# noisemaker_3-0.net
KiCad netlist of a schematic drawn in EAGLE
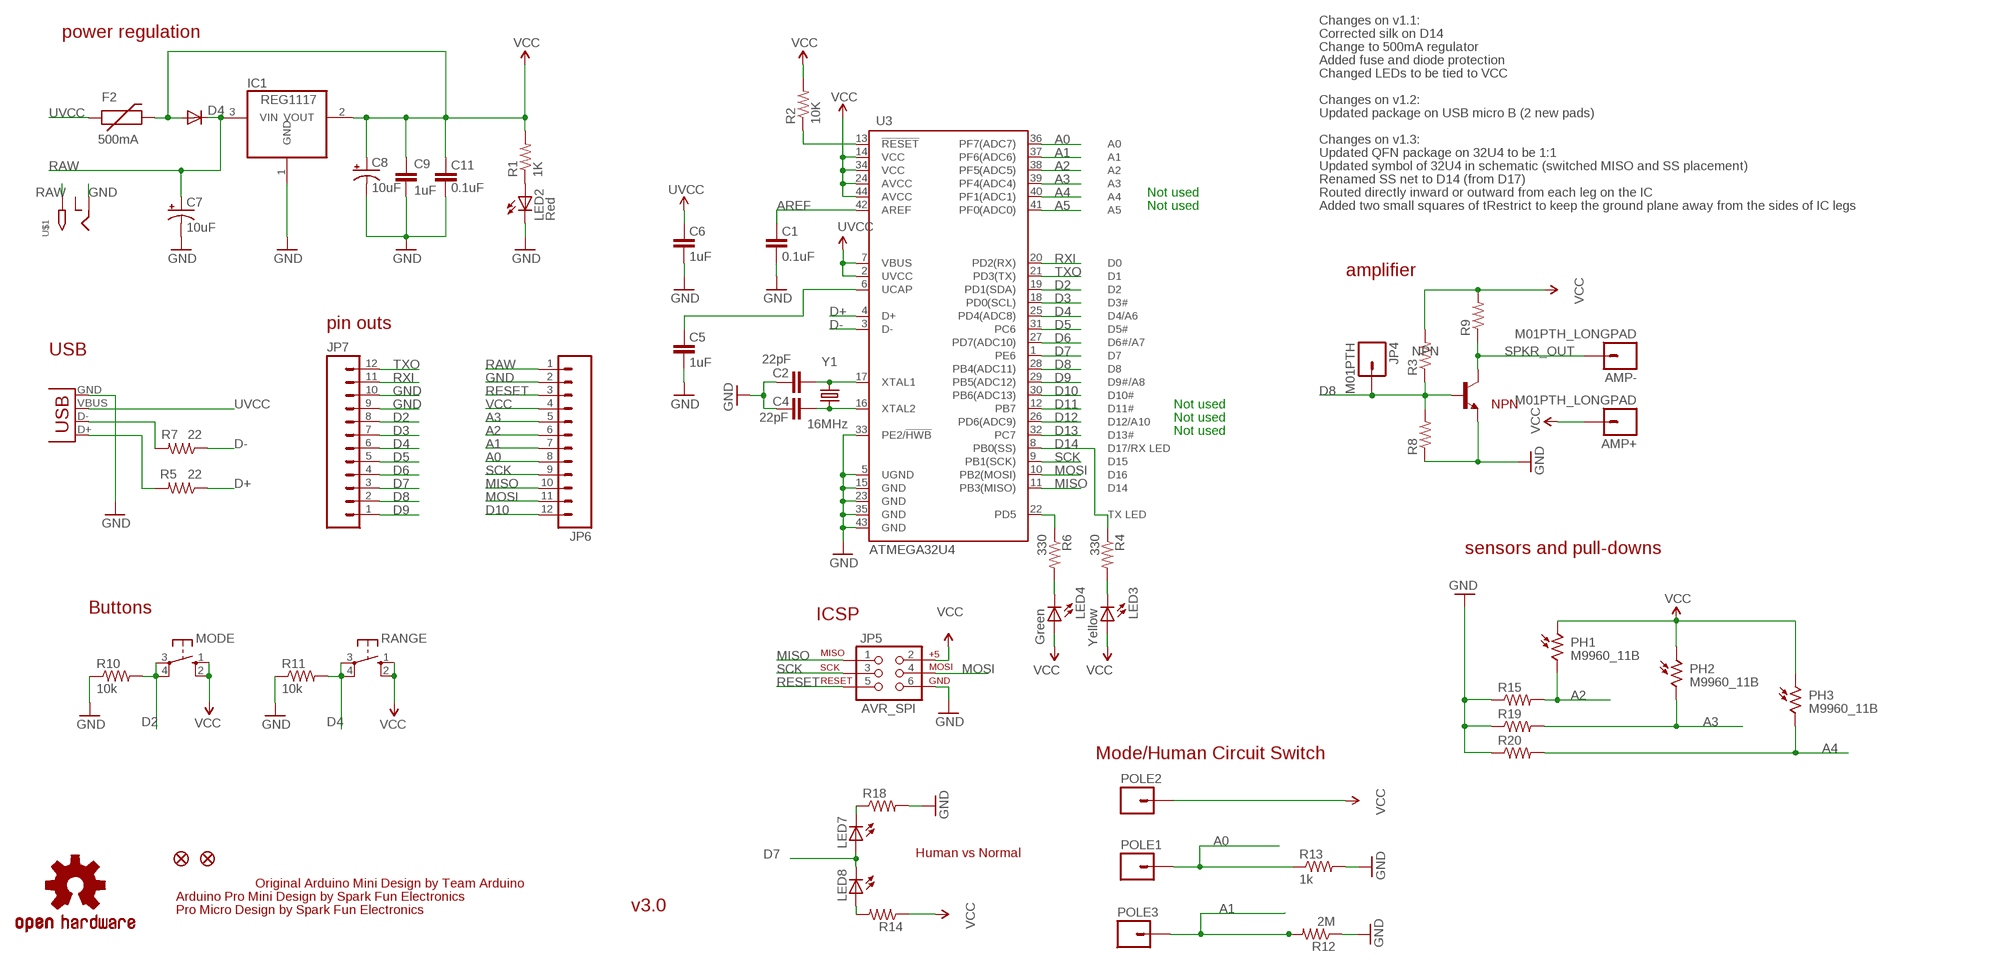
[diagram p0: schematic, sheet 1]

(export (version "E")
  (design (tool "Eeschema 10.0.6"))
  (components
    (comp (ref "AMP+")
      (value "M01PTH_LONGPAD")
      (footprint "eagle-import:1X01_LONGPAD")
      (libsource (lib "eagle-import") (part "M01PTH_LONGPAD"))
    )
    (comp (ref "AMP-")
      (value "M01PTH_LONGPAD")
      (footprint "eagle-import:1X01_LONGPAD")
      (libsource (lib "eagle-import") (part "M01PTH_LONGPAD"))
    )
    (comp (ref "C1")
      (value "0.1uF")
      (footprint "eagle-import:1206")
      (libsource (lib "eagle-import") (part "SparkFun-Capacitors_CAP1206"))
    )
    (comp (ref "C2")
      (value "22pF")
      (footprint "eagle-import:0603-CAP")
      (libsource (lib "eagle-import") (part "CAP0603-CAP"))
    )
    (comp (ref "C4")
      (value "22pF")
      (footprint "eagle-import:0603-CAP")
      (libsource (lib "eagle-import") (part "CAP0603-CAP"))
    )
    (comp (ref "C5")
      (value "1uF")
      (footprint "eagle-import:1206")
      (libsource (lib "eagle-import") (part "SparkFun-Capacitors_CAP1206"))
    )
    (comp (ref "C6")
      (value "1uF")
      (footprint "eagle-import:1206")
      (libsource (lib "eagle-import") (part "SparkFun-Capacitors_CAP1206"))
    )
    (comp (ref "C7")
      (value "10uF")
      (footprint "eagle-import:EIA3528-KIT")
      (libsource (lib "eagle-import") (part "CAP_POL3528-KIT"))
    )
    (comp (ref "C8")
      (value "10uF")
      (footprint "eagle-import:EIA3528-KIT")
      (libsource (lib "eagle-import") (part "CAP_POL3528-KIT"))
    )
    (comp (ref "C9")
      (value "1uF")
      (footprint "eagle-import:1206")
      (libsource (lib "eagle-import") (part "SparkFun-Capacitors_CAP1206"))
    )
    (comp (ref "C11")
      (value "0.1uF")
      (footprint "eagle-import:1206")
      (libsource (lib "eagle-import") (part "SparkFun-Capacitors_CAP1206"))
    )
    (comp (ref "D4")
      (value "DIODESOD")
      (footprint "eagle-import:SOD-323")
      (libsource (lib "eagle-import") (part "DIODESOD"))
    )
    (comp (ref "F2")
      (value "500mA")
      (footprint "eagle-import:PTC-1206")
      (libsource (lib "eagle-import") (part "PTCSMD"))
    )
    (comp (ref "IC1")
      (value "REG1117")
      (footprint "eagle-import:SOT223")
      (libsource (lib "eagle-import") (part "REG1117"))
    )
    (comp (ref "JP1")
      (value "FIDUCIALUFIDUCIAL")
      (footprint "eagle-import:MICRO-FIDUCIAL")
      (libsource (lib "eagle-import") (part "FIDUCIALUFIDUCIAL"))
    )
    (comp (ref "JP2")
      (value "FIDUCIALUFIDUCIAL")
      (footprint "eagle-import:MICRO-FIDUCIAL")
      (libsource (lib "eagle-import") (part "FIDUCIALUFIDUCIAL"))
    )
    (comp (ref "JP3")
      (value "USB-B")
      (footprint "eagle-import:USB-B-PTH")
      (libsource (lib "eagle-import") (part "USBPTH"))
    )
    (comp (ref "JP4")
      (value "M01PTH")
      (footprint "eagle-import:1X01")
      (libsource (lib "eagle-import") (part "M01PTH"))
    )
    (comp (ref "JP5")
      (value "AVR_SPI")
      (footprint "eagle-import:2X3")
      (libsource (lib "eagle-import") (part "AVR_SPI_PRG_6PTH"))
    )
    (comp (ref "JP6")
      (value "M12PTH")
      (footprint "eagle-import:1X12")
      (libsource (lib "eagle-import") (part "M12PTH"))
    )
    (comp (ref "JP7")
      (value "M12PTH")
      (footprint "eagle-import:1X12")
      (libsource (lib "eagle-import") (part "M12PTH"))
    )
    (comp (ref "LED2")
      (value "Red")
      (footprint "eagle-import:CHIPLED_1206")
      (libsource (lib "eagle-import") (part "LEDCHIPLED_1206"))
    )
    (comp (ref "LED3")
      (value "Yellow")
      (footprint "eagle-import:CHIPLED_1206")
      (libsource (lib "eagle-import") (part "LEDCHIPLED_1206"))
    )
    (comp (ref "LED4")
      (value "Green")
      (footprint "eagle-import:CHIPLED_1206")
      (libsource (lib "eagle-import") (part "LEDCHIPLED_1206"))
    )
    (comp (ref "LED7")
      (value "LED3MM")
      (footprint "eagle-import:LED3MM")
      (libsource (lib "eagle-import") (part "LED3MM"))
    )
    (comp (ref "LED8")
      (value "LED3MM")
      (footprint "eagle-import:LED3MM")
      (libsource (lib "eagle-import") (part "LED3MM"))
    )
    (comp (ref "MODE")
      (value "10-XX")
      (footprint "eagle-import:B3F-10XX")
      (libsource (lib "eagle-import") (part "10-XX"))
    )
    (comp (ref "NPN")
      (value "-NPN-TO220V")
      (footprint "eagle-import:TO220V")
      (libsource (lib "eagle-import") (part "-NPN-TO220V"))
    )
    (comp (ref "PH1")
      (value "M9960_11B")
      (footprint "eagle-import:M9960")
      (libsource (lib "eagle-import") (part "M9960_11B"))
    )
    (comp (ref "PH2")
      (value "M9960_11B")
      (footprint "eagle-import:M9960")
      (libsource (lib "eagle-import") (part "M9960_11B"))
    )
    (comp (ref "PH3")
      (value "M9960_11B")
      (footprint "eagle-import:M9960")
      (libsource (lib "eagle-import") (part "M9960_11B"))
    )
    (comp (ref "POLE1")
      (value "M01PTH_LONGPAD")
      (footprint "eagle-import:1X01_LONGPAD")
      (libsource (lib "eagle-import") (part "M01PTH_LONGPAD"))
    )
    (comp (ref "POLE2")
      (value "M01PTH_LONGPAD")
      (footprint "eagle-import:1X01_LONGPAD")
      (libsource (lib "eagle-import") (part "M01PTH_LONGPAD"))
    )
    (comp (ref "POLE3")
      (value "M01PTH_LONGPAD")
      (footprint "eagle-import:1X01_LONGPAD")
      (libsource (lib "eagle-import") (part "M01PTH_LONGPAD"))
    )
    (comp (ref "R1")
      (value "1K")
      (footprint "eagle-import:1206")
      (libsource (lib "eagle-import") (part "RESISTOR1206"))
    )
    (comp (ref "R2")
      (value "10K")
      (footprint "eagle-import:1206")
      (libsource (lib "eagle-import") (part "RESISTOR1206"))
    )
    (comp (ref "R3")
      (value "RESISTOR1206")
      (footprint "eagle-import:1206")
      (libsource (lib "eagle-import") (part "RESISTOR1206"))
    )
    (comp (ref "R4")
      (value "330")
      (footprint "eagle-import:1206")
      (libsource (lib "eagle-import") (part "RESISTOR1206"))
    )
    (comp (ref "R5")
      (value "22")
      (footprint "eagle-import:1206")
      (libsource (lib "eagle-import") (part "RESISTOR1206"))
    )
    (comp (ref "R6")
      (value "330")
      (footprint "eagle-import:1206")
      (libsource (lib "eagle-import") (part "RESISTOR1206"))
    )
    (comp (ref "R7")
      (value "22")
      (footprint "eagle-import:1206")
      (libsource (lib "eagle-import") (part "RESISTOR1206"))
    )
    (comp (ref "R8")
      (value "RESISTOR1206")
      (footprint "eagle-import:1206")
      (libsource (lib "eagle-import") (part "RESISTOR1206"))
    )
    (comp (ref "R9")
      (value "RESISTOR1206")
      (footprint "eagle-import:1206")
      (libsource (lib "eagle-import") (part "RESISTOR1206"))
    )
    (comp (ref "R10")
      (value "10k")
      (footprint "eagle-import:1206")
      (libsource (lib "eagle-import") (part "RESISTOR1206"))
    )
    (comp (ref "R11")
      (value "10k")
      (footprint "eagle-import:1206")
      (libsource (lib "eagle-import") (part "RESISTOR1206"))
    )
    (comp (ref "R12")
      (value "2M")
      (footprint "eagle-import:1206")
      (libsource (lib "eagle-import") (part "RESISTOR1206"))
    )
    (comp (ref "R13")
      (value "1k")
      (footprint "eagle-import:1206")
      (libsource (lib "eagle-import") (part "RESISTOR1206"))
    )
    (comp (ref "R14")
      (value "RESISTOR1206")
      (footprint "eagle-import:1206")
      (libsource (lib "eagle-import") (part "RESISTOR1206"))
    )
    (comp (ref "R15")
      (value "RESISTOR1206")
      (footprint "eagle-import:1206")
      (libsource (lib "eagle-import") (part "RESISTOR1206"))
    )
    (comp (ref "R18")
      (value "RESISTOR1206")
      (footprint "eagle-import:1206")
      (libsource (lib "eagle-import") (part "RESISTOR1206"))
    )
    (comp (ref "R19")
      (value "RESISTOR1206")
      (footprint "eagle-import:1206")
      (libsource (lib "eagle-import") (part "RESISTOR1206"))
    )
    (comp (ref "R20")
      (value "RESISTOR1206")
      (footprint "eagle-import:1206")
      (libsource (lib "eagle-import") (part "RESISTOR1206"))
    )
    (comp (ref "RANGE")
      (value "10-XX")
      (footprint "eagle-import:B3F-10XX")
      (libsource (lib "eagle-import") (part "10-XX"))
    )
    (comp (ref "U$1")
      (value "2.1MMJACKTHM")
      (footprint "eagle-import:PJ-102A")
      (libsource (lib "eagle-import") (part "2.1MMJACKTHM"))
    )
    (comp (ref "U$3")
      (value "OSHW-LOGOS")
      (footprint "eagle-import:OSHW-LOGO-S")
      (libsource (lib "eagle-import") (part "OSHW-LOGOS"))
    )
    (comp (ref "U3")
      (value "ATMEGA32U4")
      (footprint "eagle-import:SPARKFUN-DIGITALIC_TQFP44")
      (libsource (lib "eagle-import") (part "ATMEGA32U4TQFP"))
    )
    (comp (ref "Y1")
      (value "16MHz")
      (footprint "eagle-import:CRYSTAL-SMD-5X3")
      (libsource (lib "eagle-import") (part "CRYSTAL5X3"))
    )
  )
  (nets
    (net (code "1") (name "/A0") (class "Default")
      (node (ref "JP6") (pin "8") (pinfunction "8_8") (pintype "passive"))
      (node (ref "POLE1") (pin "1") (pinfunction "1_1") (pintype "passive"))
      (node (ref "R13") (pin "1") (pinfunction "1_1") (pintype "passive"))
      (node (ref "U3") (pin "36") (pinfunction "PF7(ADC7)_36") (pintype "bidirectional"))
    )
    (net (code "2") (name "/A1") (class "Default")
      (node (ref "JP6") (pin "7") (pinfunction "7_7") (pintype "passive"))
      (node (ref "POLE3") (pin "1") (pinfunction "1_1") (pintype "passive"))
      (node (ref "R12") (pin "2") (pinfunction "2_2") (pintype "passive"))
      (node (ref "U3") (pin "37") (pinfunction "PF6(ADC6)_37") (pintype "bidirectional"))
    )
    (net (code "3") (name "/A2") (class "Default")
      (node (ref "JP6") (pin "6") (pinfunction "6_6") (pintype "passive"))
      (node (ref "PH1") (pin "2") (pinfunction "2_2") (pintype "passive"))
      (node (ref "R15") (pin "2") (pinfunction "2_2") (pintype "passive"))
      (node (ref "U3") (pin "38") (pinfunction "PF5(ADC5)_38") (pintype "bidirectional"))
    )
    (net (code "4") (name "/A3") (class "Default")
      (node (ref "JP6") (pin "5") (pinfunction "5_5") (pintype "passive"))
      (node (ref "PH2") (pin "2") (pinfunction "2_2") (pintype "passive"))
      (node (ref "R19") (pin "2") (pinfunction "2_2") (pintype "passive"))
      (node (ref "U3") (pin "39") (pinfunction "PF4(ADC4)_39") (pintype "bidirectional"))
    )
    (net (code "5") (name "/A4") (class "Default")
      (node (ref "PH3") (pin "2") (pinfunction "2_2") (pintype "passive"))
      (node (ref "R20") (pin "2") (pinfunction "2_2") (pintype "passive"))
      (node (ref "U3") (pin "40") (pinfunction "PF1(ADC1)_40") (pintype "bidirectional"))
    )
    (net (code "6") (name "/A5") (class "Default")
      (node (ref "U3") (pin "41") (pinfunction "PF0(ADC0)_41") (pintype "bidirectional"))
    )
    (net (code "7") (name "/AREF") (class "Default")
      (node (ref "C1") (pin "2") (pinfunction "2_2") (pintype "passive"))
      (node (ref "U3") (pin "42") (pinfunction "AREF_42") (pintype "bidirectional"))
    )
    (net (code "8") (name "/D+") (class "Default")
      (node (ref "R5") (pin "1") (pinfunction "1_1") (pintype "passive"))
      (node (ref "U3") (pin "4") (pinfunction "D+_4") (pintype "bidirectional"))
    )
    (net (code "9") (name "/D-") (class "Default")
      (node (ref "R7") (pin "1") (pinfunction "1_1") (pintype "passive"))
      (node (ref "U3") (pin "3") (pinfunction "D-_3") (pintype "bidirectional"))
    )
    (net (code "10") (name "/D2") (class "Default")
      (node (ref "JP7") (pin "8") (pinfunction "8_8") (pintype "passive"))
      (node (ref "MODE") (pin "3") (pinfunction "P_3") (pintype "passive"))
      (node (ref "MODE") (pin "4") (pinfunction "P1_4") (pintype "passive"))
      (node (ref "R10") (pin "2") (pinfunction "2_2") (pintype "passive"))
      (node (ref "U3") (pin "19") (pinfunction "PD1(SDA)_19") (pintype "bidirectional"))
    )
    (net (code "11") (name "/D3") (class "Default")
      (node (ref "JP7") (pin "7") (pinfunction "7_7") (pintype "passive"))
      (node (ref "U3") (pin "18") (pinfunction "PD0(SCL)_18") (pintype "bidirectional"))
    )
    (net (code "12") (name "/D4") (class "Default")
      (node (ref "JP7") (pin "6") (pinfunction "6_6") (pintype "passive"))
      (node (ref "R11") (pin "2") (pinfunction "2_2") (pintype "passive"))
      (node (ref "RANGE") (pin "3") (pinfunction "P_3") (pintype "passive"))
      (node (ref "RANGE") (pin "4") (pinfunction "P1_4") (pintype "passive"))
      (node (ref "U3") (pin "25") (pinfunction "PD4(ADC8)_25") (pintype "bidirectional"))
    )
    (net (code "13") (name "/D5") (class "Default")
      (node (ref "JP7") (pin "5") (pinfunction "5_5") (pintype "passive"))
      (node (ref "U3") (pin "31") (pinfunction "PC6_31") (pintype "bidirectional"))
    )
    (net (code "14") (name "/D6") (class "Default")
      (node (ref "JP7") (pin "4") (pinfunction "4_4") (pintype "passive"))
      (node (ref "U3") (pin "27") (pinfunction "PD7(ADC10)_27") (pintype "bidirectional"))
    )
    (net (code "15") (name "/D7") (class "Default")
      (node (ref "JP7") (pin "3") (pinfunction "3_3") (pintype "passive"))
      (node (ref "LED7") (pin "A") (pinfunction "A_A") (pintype "passive"))
      (node (ref "LED8") (pin "K") (pinfunction "C_K") (pintype "passive"))
      (node (ref "U3") (pin "1") (pinfunction "PE6_1") (pintype "bidirectional"))
    )
    (net (code "16") (name "/D8") (class "Default")
      (node (ref "JP4") (pin "1") (pinfunction "1_1") (pintype "passive"))
      (node (ref "JP7") (pin "2") (pinfunction "2_2") (pintype "passive"))
      (node (ref "NPN") (pin "1") (pinfunction "B_1") (pintype "passive"))
      (node (ref "R3") (pin "1") (pinfunction "1_1") (pintype "passive"))
      (node (ref "R8") (pin "2") (pinfunction "2_2") (pintype "passive"))
      (node (ref "U3") (pin "28") (pinfunction "PB4(ADC11)_28") (pintype "bidirectional"))
    )
    (net (code "17") (name "/D9") (class "Default")
      (node (ref "JP7") (pin "1") (pinfunction "1_1") (pintype "passive"))
      (node (ref "U3") (pin "29") (pinfunction "PB5(ADC12)_29") (pintype "bidirectional"))
    )
    (net (code "18") (name "/D10") (class "Default")
      (node (ref "JP6") (pin "12") (pinfunction "12_12") (pintype "passive"))
      (node (ref "U3") (pin "30") (pinfunction "PB6(ADC13)_30") (pintype "bidirectional"))
    )
    (net (code "19") (name "/D11") (class "Default")
      (node (ref "U3") (pin "12") (pinfunction "PB7_12") (pintype "bidirectional"))
    )
    (net (code "20") (name "/D12") (class "Default")
      (node (ref "U3") (pin "26") (pinfunction "PD6(ADC9)_26") (pintype "bidirectional"))
    )
    (net (code "21") (name "/D13") (class "Default")
      (node (ref "U3") (pin "32") (pinfunction "PC7_32") (pintype "bidirectional"))
    )
    (net (code "22") (name "/D14") (class "Default")
      (node (ref "R4") (pin "1") (pinfunction "1_1") (pintype "passive"))
      (node (ref "U3") (pin "8") (pinfunction "PB0(SS)_8") (pintype "bidirectional"))
    )
    (net (code "23") (name "/MISO") (class "Default")
      (node (ref "JP5") (pin "1") (pinfunction "1_1") (pintype "passive"))
      (node (ref "JP6") (pin "10") (pinfunction "10_10") (pintype "passive"))
      (node (ref "U3") (pin "11") (pinfunction "PB3(MISO)_11") (pintype "bidirectional"))
    )
    (net (code "24") (name "/MOSI") (class "Default")
      (node (ref "JP5") (pin "4") (pinfunction "4_4") (pintype "passive"))
      (node (ref "JP6") (pin "11") (pinfunction "11_11") (pintype "passive"))
      (node (ref "U3") (pin "10") (pinfunction "PB2(MOSI)_10") (pintype "bidirectional"))
    )
    (net (code "25") (name "/RAW") (class "Default")
      (node (ref "C7") (pin "A") (pinfunction "+_A") (pintype "passive"))
      (node (ref "D4") (pin "1") (pinfunction "C_1") (pintype "passive"))
      (node (ref "IC1") (pin "3") (pinfunction "VIN_3") (pintype "input"))
      (node (ref "JP6") (pin "1") (pinfunction "1_1") (pintype "passive"))
      (node (ref "U$1") (pin "TIP") (pinfunction "TIP_TIP") (pintype "bidirectional"))
    )
    (net (code "26") (name "/RESET") (class "Default")
      (node (ref "JP5") (pin "5") (pinfunction "5_5") (pintype "passive"))
      (node (ref "JP6") (pin "3") (pinfunction "3_3") (pintype "passive"))
      (node (ref "R2") (pin "1") (pinfunction "1_1") (pintype "passive"))
      (node (ref "U3") (pin "13") (pinfunction "~{RESET}_13") (pintype "bidirectional"))
    )
    (net (code "27") (name "/RXI") (class "Default")
      (node (ref "JP7") (pin "11") (pinfunction "11_11") (pintype "passive"))
      (node (ref "U3") (pin "20") (pinfunction "PD2(RX)_20") (pintype "bidirectional"))
    )
    (net (code "28") (name "/SCK") (class "Default")
      (node (ref "JP5") (pin "3") (pinfunction "3_3") (pintype "passive"))
      (node (ref "JP6") (pin "9") (pinfunction "9_9") (pintype "passive"))
      (node (ref "U3") (pin "9") (pinfunction "PB1(SCK)_9") (pintype "bidirectional"))
    )
    (net (code "29") (name "/SPKR_OUT") (class "Default")
      (node (ref "AMP-") (pin "1") (pinfunction "1_1") (pintype "passive"))
      (node (ref "NPN") (pin "2") (pinfunction "C_2") (pintype "passive"))
      (node (ref "R9") (pin "1") (pinfunction "1_1") (pintype "passive"))
    )
    (net (code "30") (name "/TXO") (class "Default")
      (node (ref "JP7") (pin "12") (pinfunction "12_12") (pintype "passive"))
      (node (ref "U3") (pin "21") (pinfunction "PD3(TX)_21") (pintype "bidirectional"))
    )
    (net (code "31") (name "GND") (class "Default")
      (node (ref "C1") (pin "1") (pinfunction "1_1") (pintype "passive"))
      (node (ref "C11") (pin "1") (pinfunction "1_1") (pintype "passive"))
      (node (ref "C2") (pin "2") (pinfunction "2_2") (pintype "passive"))
      (node (ref "C4") (pin "2") (pinfunction "2_2") (pintype "passive"))
      (node (ref "C5") (pin "1") (pinfunction "1_1") (pintype "passive"))
      (node (ref "C6") (pin "1") (pinfunction "1_1") (pintype "passive"))
      (node (ref "C7") (pin "C") (pinfunction "-_C") (pintype "passive"))
      (node (ref "C8") (pin "C") (pinfunction "-_C") (pintype "passive"))
      (node (ref "C9") (pin "2") (pinfunction "2_2") (pintype "passive"))
      (node (ref "IC1") (pin "1") (pinfunction "GND_1") (pintype "power_in"))
      (node (ref "JP3") (pin "GND") (pinfunction "GND_GND") (pintype "bidirectional"))
      (node (ref "JP5") (pin "6") (pinfunction "6_6") (pintype "passive"))
      (node (ref "JP6") (pin "2") (pinfunction "2_2") (pintype "passive"))
      (node (ref "JP7") (pin "10") (pinfunction "10_10") (pintype "passive"))
      (node (ref "JP7") (pin "9") (pinfunction "9_9") (pintype "passive"))
      (node (ref "LED2") (pin "C") (pinfunction "C_C") (pintype "passive"))
      (node (ref "NPN") (pin "3") (pinfunction "E_3") (pintype "passive"))
      (node (ref "R10") (pin "1") (pinfunction "1_1") (pintype "passive"))
      (node (ref "R11") (pin "1") (pinfunction "1_1") (pintype "passive"))
      (node (ref "R12") (pin "1") (pinfunction "1_1") (pintype "passive"))
      (node (ref "R13") (pin "2") (pinfunction "2_2") (pintype "passive"))
      (node (ref "R15") (pin "1") (pinfunction "1_1") (pintype "passive"))
      (node (ref "R18") (pin "2") (pinfunction "2_2") (pintype "passive"))
      (node (ref "R19") (pin "1") (pinfunction "1_1") (pintype "passive"))
      (node (ref "R20") (pin "1") (pinfunction "1_1") (pintype "passive"))
      (node (ref "R8") (pin "1") (pinfunction "1_1") (pintype "passive"))
      (node (ref "U$1") (pin "RING") (pinfunction "RING_RING") (pintype "bidirectional"))
      (node (ref "U3") (pin "15") (pinfunction "GND_15") (pintype "bidirectional"))
      (node (ref "U3") (pin "23") (pinfunction "GND_23") (pintype "bidirectional"))
      (node (ref "U3") (pin "33") (pinfunction "PE2/~{HWB}_33") (pintype "bidirectional"))
      (node (ref "U3") (pin "35") (pinfunction "GND_35") (pintype "bidirectional"))
      (node (ref "U3") (pin "43") (pinfunction "GND_43") (pintype "bidirectional"))
      (node (ref "U3") (pin "5") (pinfunction "UGND_5") (pintype "bidirectional"))
    )
    (net (code "32") (name "Net-(JP3-PadD+)") (class "Default")
      (node (ref "JP3") (pin "D+") (pinfunction "D+_D+") (pintype "bidirectional"))
      (node (ref "R5") (pin "2") (pinfunction "2_2") (pintype "passive"))
    )
    (net (code "33") (name "Net-(JP3-PadD-)") (class "Default")
      (node (ref "JP3") (pin "D-") (pinfunction "D-_D-") (pintype "bidirectional"))
      (node (ref "R7") (pin "2") (pinfunction "2_2") (pintype "passive"))
    )
    (net (code "34") (name "Net-(LED2-PadA)") (class "Default")
      (node (ref "LED2") (pin "A") (pinfunction "A_A") (pintype "passive"))
      (node (ref "R1") (pin "1") (pinfunction "1_1") (pintype "passive"))
    )
    (net (code "35") (name "Net-(LED3-PadC)") (class "Default")
      (node (ref "LED3") (pin "C") (pinfunction "C_C") (pintype "passive"))
      (node (ref "R4") (pin "2") (pinfunction "2_2") (pintype "passive"))
    )
    (net (code "36") (name "Net-(LED4-PadC)") (class "Default")
      (node (ref "LED4") (pin "C") (pinfunction "C_C") (pintype "passive"))
      (node (ref "R6") (pin "2") (pinfunction "2_2") (pintype "passive"))
    )
    (net (code "37") (name "Net-(LED7-C)") (class "Default")
      (node (ref "LED7") (pin "K") (pinfunction "C_K") (pintype "passive"))
      (node (ref "R18") (pin "1") (pinfunction "1_1") (pintype "passive"))
    )
    (net (code "38") (name "Net-(LED8-PadA)") (class "Default")
      (node (ref "LED8") (pin "A") (pinfunction "A_A") (pintype "passive"))
      (node (ref "R14") (pin "2") (pinfunction "2_2") (pintype "passive"))
    )
    (net (code "39") (name "Net-(U3-PD5)") (class "Default")
      (node (ref "R6") (pin "1") (pinfunction "1_1") (pintype "passive"))
      (node (ref "U3") (pin "22") (pinfunction "PD5_22") (pintype "bidirectional"))
    )
    (net (code "40") (name "Net-(U3-UCAP)") (class "Default")
      (node (ref "C5") (pin "2") (pinfunction "2_2") (pintype "passive"))
      (node (ref "U3") (pin "6") (pinfunction "UCAP_6") (pintype "bidirectional"))
    )
    (net (code "41") (name "Net-(U3-XTAL1)") (class "Default")
      (node (ref "C2") (pin "1") (pinfunction "1_1") (pintype "passive"))
      (node (ref "U3") (pin "17") (pinfunction "XTAL1_17") (pintype "bidirectional"))
      (node (ref "Y1") (pin "3") (pinfunction "2_3") (pintype "passive"))
    )
    (net (code "42") (name "Net-(U3-XTAL2)") (class "Default")
      (node (ref "C4") (pin "1") (pinfunction "1_1") (pintype "passive"))
      (node (ref "U3") (pin "16") (pinfunction "XTAL2_16") (pintype "bidirectional"))
      (node (ref "Y1") (pin "1") (pinfunction "1_1") (pintype "passive"))
    )
    (net (code "43") (name "UVCC") (class "Default")
      (node (ref "C6") (pin "2") (pinfunction "2_2") (pintype "passive"))
      (node (ref "F2") (pin "1") (pinfunction "1_1") (pintype "bidirectional"))
      (node (ref "JP3") (pin "VBUS") (pinfunction "VBUS_VBUS") (pintype "bidirectional"))
      (node (ref "U3") (pin "2") (pinfunction "UVCC_2") (pintype "bidirectional"))
      (node (ref "U3") (pin "7") (pinfunction "VBUS_7") (pintype "bidirectional"))
    )
    (net (code "44") (name "VCC") (class "Default")
      (node (ref "AMP+") (pin "1") (pinfunction "1_1") (pintype "passive"))
      (node (ref "C11") (pin "2") (pinfunction "2_2") (pintype "passive"))
      (node (ref "C8") (pin "A") (pinfunction "+_A") (pintype "passive"))
      (node (ref "C9") (pin "1") (pinfunction "1_1") (pintype "passive"))
      (node (ref "D4") (pin "2") (pinfunction "A_2") (pintype "passive"))
      (node (ref "F2") (pin "2") (pinfunction "2_2") (pintype "bidirectional"))
      (node (ref "IC1") (pin "2") (pinfunction "VOUT_2") (pintype "output"))
      (node (ref "JP5") (pin "2") (pinfunction "2_2") (pintype "passive"))
      (node (ref "JP6") (pin "4") (pinfunction "4_4") (pintype "passive"))
      (node (ref "LED3") (pin "A") (pinfunction "A_A") (pintype "passive"))
      (node (ref "LED4") (pin "A") (pinfunction "A_A") (pintype "passive"))
      (node (ref "MODE") (pin "1") (pinfunction "S_1") (pintype "passive"))
      (node (ref "MODE") (pin "2") (pinfunction "S1_2") (pintype "passive"))
      (node (ref "PH1") (pin "1") (pinfunction "1_1") (pintype "passive"))
      (node (ref "PH2") (pin "1") (pinfunction "1_1") (pintype "passive"))
      (node (ref "PH3") (pin "1") (pinfunction "1_1") (pintype "passive"))
      (node (ref "POLE2") (pin "1") (pinfunction "1_1") (pintype "passive"))
      (node (ref "R1") (pin "2") (pinfunction "2_2") (pintype "passive"))
      (node (ref "R14") (pin "1") (pinfunction "1_1") (pintype "passive"))
      (node (ref "R2") (pin "2") (pinfunction "2_2") (pintype "passive"))
      (node (ref "R3") (pin "2") (pinfunction "2_2") (pintype "passive"))
      (node (ref "R9") (pin "2") (pinfunction "2_2") (pintype "passive"))
      (node (ref "RANGE") (pin "1") (pinfunction "S_1") (pintype "passive"))
      (node (ref "RANGE") (pin "2") (pinfunction "S1_2") (pintype "passive"))
      (node (ref "U3") (pin "14") (pinfunction "VCC_14") (pintype "bidirectional"))
      (node (ref "U3") (pin "24") (pinfunction "AVCC_24") (pintype "bidirectional"))
      (node (ref "U3") (pin "34") (pinfunction "VCC_34") (pintype "bidirectional"))
      (node (ref "U3") (pin "44") (pinfunction "AVCC_44") (pintype "bidirectional"))
    )
    (net (code "45") (name "unconnected-(U$1-PadRING_SW)") (class "Default")
      (node (ref "U$1") (pin "RING_SW") (pinfunction "RING_SW_RING_SW") (pintype "bidirectional"))
    )
  )
)
